# LED_Controller.net
KiCad netlist of a schematic drawn in EAGLE
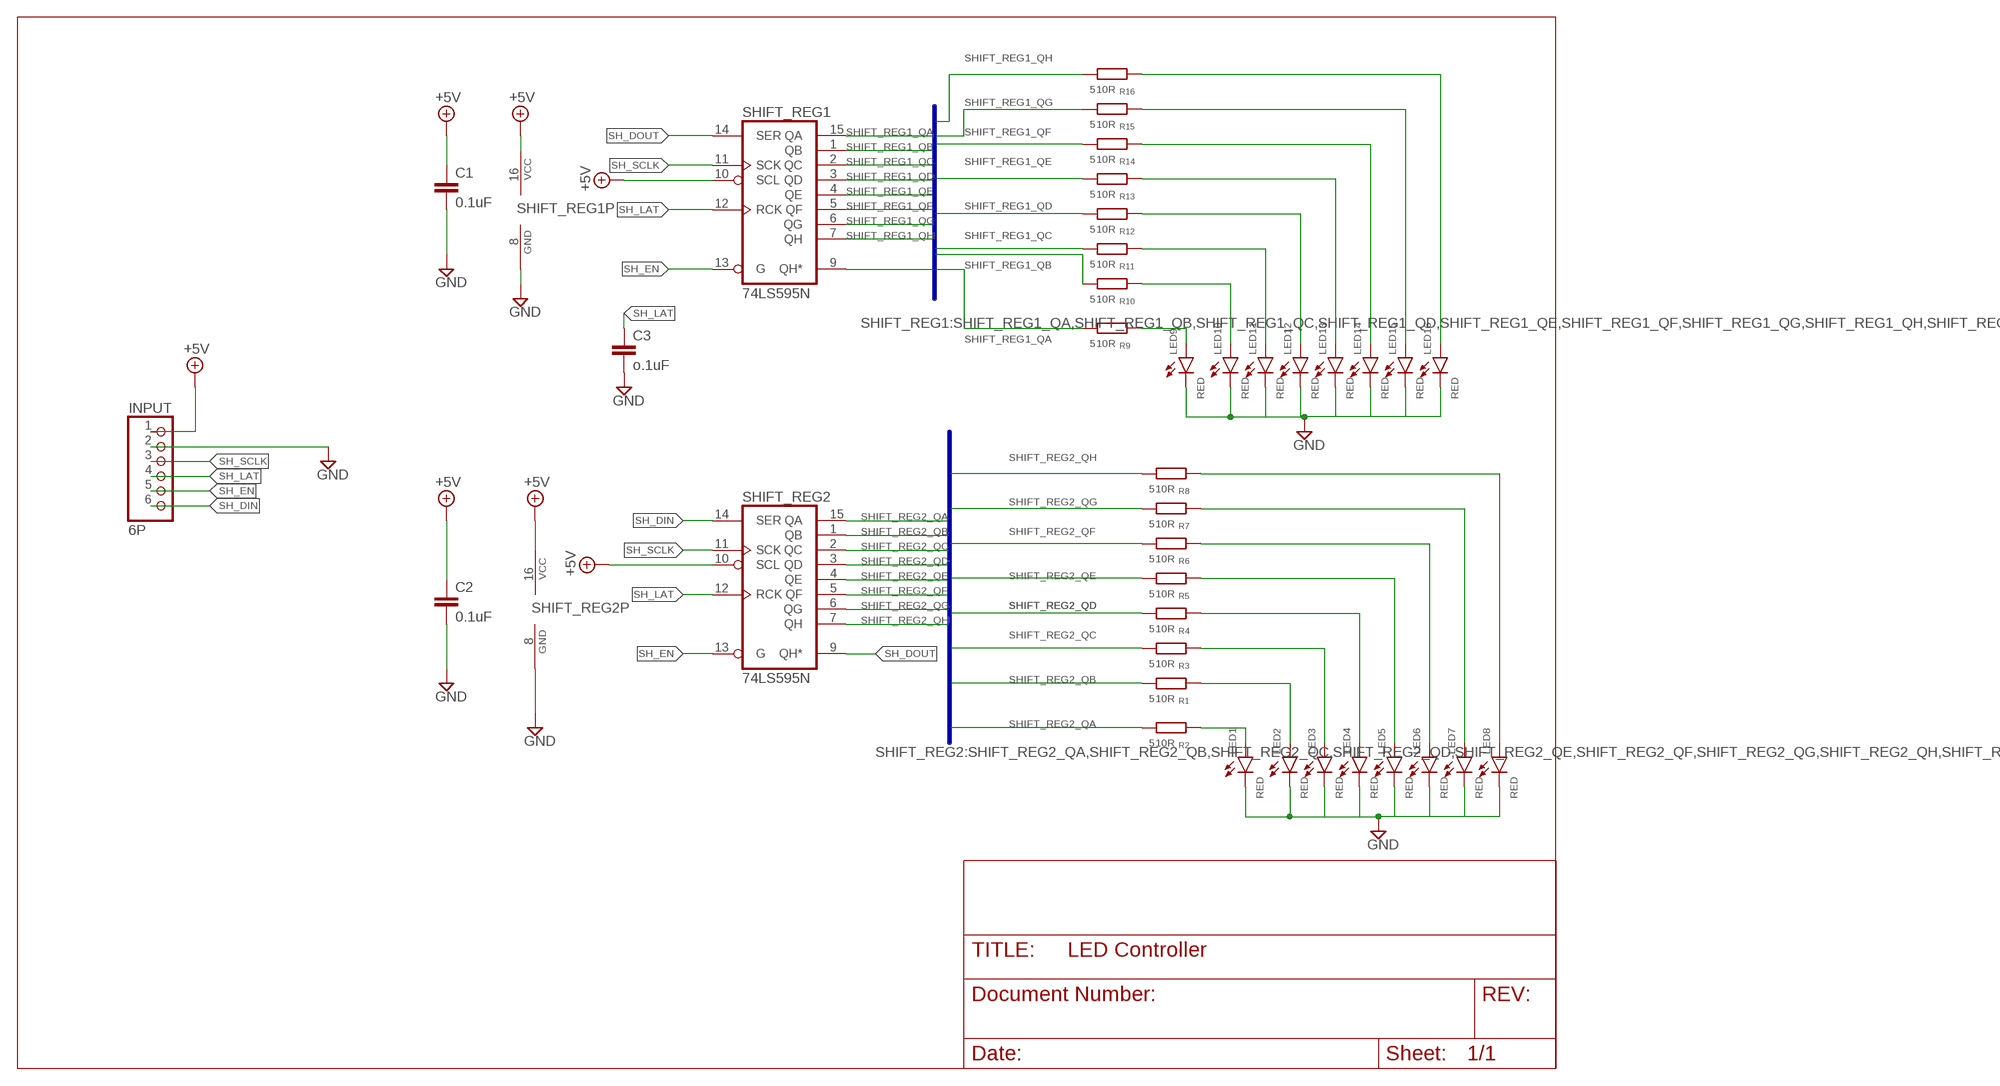
[diagram p0: schematic, sheet 1]

(export (version "E")
  (design (tool "Eeschema 10.0.6"))
  (components
    (comp (ref "C1")
      (value "0.1uF")
      (footprint "eagle-import:C050-030X075")
      (libsource (lib "eagle-import") (part "C-EU050-030X075"))
    )
    (comp (ref "C2")
      (value "0.1uF")
      (footprint "eagle-import:C050-030X075")
      (libsource (lib "eagle-import") (part "C-EU050-030X075"))
    )
    (comp (ref "C3")
      (value "o.1uF")
      (footprint "eagle-import:C050-030X075")
      (libsource (lib "eagle-import") (part "C-EU050-030X075"))
    )
    (comp (ref "INPUT")
      (value "6P")
      (footprint "eagle-import:1X06_90")
      (libsource (lib "eagle-import") (part "PINHD-1X6/90"))
    )
    (comp (ref "LED1")
      (value "RED")
      (footprint "eagle-import:LED5MM")
      (libsource (lib "eagle-import") (part "LED5MM"))
    )
    (comp (ref "LED2")
      (value "RED")
      (footprint "eagle-import:LED5MM")
      (libsource (lib "eagle-import") (part "LED5MM"))
    )
    (comp (ref "LED3")
      (value "RED")
      (footprint "eagle-import:LED5MM")
      (libsource (lib "eagle-import") (part "LED5MM"))
    )
    (comp (ref "LED4")
      (value "RED")
      (footprint "eagle-import:LED5MM")
      (libsource (lib "eagle-import") (part "LED5MM"))
    )
    (comp (ref "LED5")
      (value "RED")
      (footprint "eagle-import:LED5MM")
      (libsource (lib "eagle-import") (part "LED5MM"))
    )
    (comp (ref "LED6")
      (value "RED")
      (footprint "eagle-import:LED5MM")
      (libsource (lib "eagle-import") (part "LED5MM"))
    )
    (comp (ref "LED7")
      (value "RED")
      (footprint "eagle-import:LED5MM")
      (libsource (lib "eagle-import") (part "LED5MM"))
    )
    (comp (ref "LED8")
      (value "RED")
      (footprint "eagle-import:LED5MM")
      (libsource (lib "eagle-import") (part "LED5MM"))
    )
    (comp (ref "LED9")
      (value "RED")
      (footprint "eagle-import:LED5MM")
      (libsource (lib "eagle-import") (part "LED5MM"))
    )
    (comp (ref "LED10")
      (value "RED")
      (footprint "eagle-import:LED5MM")
      (libsource (lib "eagle-import") (part "LED5MM"))
    )
    (comp (ref "LED11")
      (value "RED")
      (footprint "eagle-import:LED5MM")
      (libsource (lib "eagle-import") (part "LED5MM"))
    )
    (comp (ref "LED12")
      (value "RED")
      (footprint "eagle-import:LED5MM")
      (libsource (lib "eagle-import") (part "LED5MM"))
    )
    (comp (ref "LED13")
      (value "RED")
      (footprint "eagle-import:LED5MM")
      (libsource (lib "eagle-import") (part "LED5MM"))
    )
    (comp (ref "LED14")
      (value "RED")
      (footprint "eagle-import:LED5MM")
      (libsource (lib "eagle-import") (part "LED5MM"))
    )
    (comp (ref "LED15")
      (value "RED")
      (footprint "eagle-import:LED5MM")
      (libsource (lib "eagle-import") (part "LED5MM"))
    )
    (comp (ref "LED16")
      (value "RED")
      (footprint "eagle-import:LED5MM")
      (libsource (lib "eagle-import") (part "LED5MM"))
    )
    (comp (ref "R1")
      (value "510R")
      (footprint "eagle-import:0207_10")
      (libsource (lib "eagle-import") (part "R-EU_0207/10"))
    )
    (comp (ref "R2")
      (value "510R")
      (footprint "eagle-import:0207_10")
      (libsource (lib "eagle-import") (part "R-EU_0207/10"))
    )
    (comp (ref "R3")
      (value "510R")
      (footprint "eagle-import:0207_10")
      (libsource (lib "eagle-import") (part "R-EU_0207/10"))
    )
    (comp (ref "R4")
      (value "510R")
      (footprint "eagle-import:0207_10")
      (libsource (lib "eagle-import") (part "R-EU_0207/10"))
    )
    (comp (ref "R5")
      (value "510R")
      (footprint "eagle-import:0207_10")
      (libsource (lib "eagle-import") (part "R-EU_0207/10"))
    )
    (comp (ref "R6")
      (value "510R")
      (footprint "eagle-import:0207_10")
      (libsource (lib "eagle-import") (part "R-EU_0207/10"))
    )
    (comp (ref "R7")
      (value "510R")
      (footprint "eagle-import:0207_10")
      (libsource (lib "eagle-import") (part "R-EU_0207/10"))
    )
    (comp (ref "R8")
      (value "510R")
      (footprint "eagle-import:0207_10")
      (libsource (lib "eagle-import") (part "R-EU_0207/10"))
    )
    (comp (ref "R9")
      (value "510R")
      (footprint "eagle-import:0207_10")
      (libsource (lib "eagle-import") (part "R-EU_0207/10"))
    )
    (comp (ref "R10")
      (value "510R")
      (footprint "eagle-import:0207_10")
      (libsource (lib "eagle-import") (part "R-EU_0207/10"))
    )
    (comp (ref "R11")
      (value "510R")
      (footprint "eagle-import:0207_10")
      (libsource (lib "eagle-import") (part "R-EU_0207/10"))
    )
    (comp (ref "R12")
      (value "510R")
      (footprint "eagle-import:0207_10")
      (libsource (lib "eagle-import") (part "R-EU_0207/10"))
    )
    (comp (ref "R13")
      (value "510R")
      (footprint "eagle-import:0207_10")
      (libsource (lib "eagle-import") (part "R-EU_0207/10"))
    )
    (comp (ref "R14")
      (value "510R")
      (footprint "eagle-import:0207_10")
      (libsource (lib "eagle-import") (part "R-EU_0207/10"))
    )
    (comp (ref "R15")
      (value "510R")
      (footprint "eagle-import:0207_10")
      (libsource (lib "eagle-import") (part "R-EU_0207/10"))
    )
    (comp (ref "R16")
      (value "510R")
      (footprint "eagle-import:0207_10")
      (libsource (lib "eagle-import") (part "R-EU_0207/10"))
    )
    (comp (ref "SHIFT_REG1")
      (value "74LS595N")
      (footprint "eagle-import:DIL16")
      (libsource (lib "eagle-import") (part "74595NLS"))
    )
    (comp (ref "SHIFT_REG2")
      (value "74LS595N")
      (footprint "eagle-import:DIL16")
      (libsource (lib "eagle-import") (part "74595NLS"))
    )
  )
  (nets
    (net (code "5") (name "+5V") (class "Default")
      (node (ref "C1") (pin "1") (pinfunction "1_1") (pintype "passive"))
      (node (ref "C2") (pin "1") (pinfunction "1_1") (pintype "passive"))
      (node (ref "INPUT") (pin "1") (pinfunction "1_1") (pintype "passive"))
      (node (ref "SHIFT_REG1") (pin "10") (pinfunction "SCL_10") (pintype "input"))
      (node (ref "SHIFT_REG1") (pin "16") (pinfunction "VCC_16") (pintype "power_in"))
      (node (ref "SHIFT_REG2") (pin "10") (pinfunction "SCL_10") (pintype "input"))
      (node (ref "SHIFT_REG2") (pin "16") (pinfunction "VCC_16") (pintype "power_in"))
    )
    (net (code "6") (name "/SHIFT_REG1_QA") (class "Default")
      (node (ref "R9") (pin "1") (pinfunction "1_1") (pintype "passive"))
      (node (ref "SHIFT_REG1") (pin "15") (pinfunction "QA_15") (pintype "tri_state"))
    )
    (net (code "7") (name "/SHIFT_REG1_QB") (class "Default")
      (node (ref "R10") (pin "1") (pinfunction "1_1") (pintype "passive"))
      (node (ref "SHIFT_REG1") (pin "1") (pinfunction "QB_1") (pintype "tri_state"))
    )
    (net (code "8") (name "/SHIFT_REG1_QC") (class "Default")
      (node (ref "R11") (pin "1") (pinfunction "1_1") (pintype "passive"))
      (node (ref "SHIFT_REG1") (pin "2") (pinfunction "QC_2") (pintype "tri_state"))
    )
    (net (code "9") (name "/SHIFT_REG1_QD") (class "Default")
      (node (ref "R12") (pin "1") (pinfunction "1_1") (pintype "passive"))
      (node (ref "SHIFT_REG1") (pin "3") (pinfunction "QD_3") (pintype "tri_state"))
    )
    (net (code "10") (name "/SHIFT_REG1_QE") (class "Default")
      (node (ref "R13") (pin "1") (pinfunction "1_1") (pintype "passive"))
      (node (ref "SHIFT_REG1") (pin "4") (pinfunction "QE_4") (pintype "tri_state"))
    )
    (net (code "11") (name "/SHIFT_REG1_QF") (class "Default")
      (node (ref "R14") (pin "1") (pinfunction "1_1") (pintype "passive"))
      (node (ref "SHIFT_REG1") (pin "5") (pinfunction "QF_5") (pintype "tri_state"))
    )
    (net (code "12") (name "/SHIFT_REG1_QG") (class "Default")
      (node (ref "R15") (pin "1") (pinfunction "1_1") (pintype "passive"))
      (node (ref "SHIFT_REG1") (pin "6") (pinfunction "QG_6") (pintype "tri_state"))
    )
    (net (code "13") (name "/SHIFT_REG1_QH") (class "Default")
      (node (ref "R16") (pin "1") (pinfunction "1_1") (pintype "passive"))
      (node (ref "SHIFT_REG1") (pin "7") (pinfunction "QH_7") (pintype "tri_state"))
    )
    (net (code "14") (name "/SHIFT_REG2_QA") (class "Default")
      (node (ref "R2") (pin "1") (pinfunction "1_1") (pintype "passive"))
      (node (ref "SHIFT_REG2") (pin "15") (pinfunction "QA_15") (pintype "tri_state"))
    )
    (net (code "15") (name "/SHIFT_REG2_QB") (class "Default")
      (node (ref "R1") (pin "1") (pinfunction "1_1") (pintype "passive"))
      (node (ref "SHIFT_REG2") (pin "1") (pinfunction "QB_1") (pintype "tri_state"))
    )
    (net (code "16") (name "/SHIFT_REG2_QC") (class "Default")
      (node (ref "R3") (pin "1") (pinfunction "1_1") (pintype "passive"))
      (node (ref "SHIFT_REG2") (pin "2") (pinfunction "QC_2") (pintype "tri_state"))
    )
    (net (code "17") (name "/SHIFT_REG2_QD") (class "Default")
      (node (ref "R4") (pin "1") (pinfunction "1_1") (pintype "passive"))
      (node (ref "SHIFT_REG2") (pin "3") (pinfunction "QD_3") (pintype "tri_state"))
    )
    (net (code "18") (name "/SHIFT_REG2_QE") (class "Default")
      (node (ref "R5") (pin "1") (pinfunction "1_1") (pintype "passive"))
      (node (ref "SHIFT_REG2") (pin "4") (pinfunction "QE_4") (pintype "tri_state"))
    )
    (net (code "19") (name "/SHIFT_REG2_QF") (class "Default")
      (node (ref "R6") (pin "1") (pinfunction "1_1") (pintype "passive"))
      (node (ref "SHIFT_REG2") (pin "5") (pinfunction "QF_5") (pintype "tri_state"))
    )
    (net (code "20") (name "/SHIFT_REG2_QG") (class "Default")
      (node (ref "R7") (pin "1") (pinfunction "1_1") (pintype "passive"))
      (node (ref "SHIFT_REG2") (pin "6") (pinfunction "QG_6") (pintype "tri_state"))
    )
    (net (code "21") (name "/SHIFT_REG2_QH") (class "Default")
      (node (ref "R8") (pin "1") (pinfunction "1_1") (pintype "passive"))
      (node (ref "SHIFT_REG2") (pin "7") (pinfunction "QH_7") (pintype "tri_state"))
    )
    (net (code "24") (name "GND") (class "Default")
      (node (ref "C1") (pin "2") (pinfunction "2_2") (pintype "passive"))
      (node (ref "C2") (pin "2") (pinfunction "2_2") (pintype "passive"))
      (node (ref "C3") (pin "2") (pinfunction "2_2") (pintype "passive"))
      (node (ref "INPUT") (pin "2") (pinfunction "2_2") (pintype "passive"))
      (node (ref "LED1") (pin "K") (pinfunction "C_K") (pintype "passive"))
      (node (ref "LED10") (pin "K") (pinfunction "C_K") (pintype "passive"))
      (node (ref "LED11") (pin "K") (pinfunction "C_K") (pintype "passive"))
      (node (ref "LED12") (pin "K") (pinfunction "C_K") (pintype "passive"))
      (node (ref "LED13") (pin "K") (pinfunction "C_K") (pintype "passive"))
      (node (ref "LED14") (pin "K") (pinfunction "C_K") (pintype "passive"))
      (node (ref "LED15") (pin "K") (pinfunction "C_K") (pintype "passive"))
      (node (ref "LED16") (pin "K") (pinfunction "C_K") (pintype "passive"))
      (node (ref "LED2") (pin "K") (pinfunction "C_K") (pintype "passive"))
      (node (ref "LED3") (pin "K") (pinfunction "C_K") (pintype "passive"))
      (node (ref "LED4") (pin "K") (pinfunction "C_K") (pintype "passive"))
      (node (ref "LED5") (pin "K") (pinfunction "C_K") (pintype "passive"))
      (node (ref "LED6") (pin "K") (pinfunction "C_K") (pintype "passive"))
      (node (ref "LED7") (pin "K") (pinfunction "C_K") (pintype "passive"))
      (node (ref "LED8") (pin "K") (pinfunction "C_K") (pintype "passive"))
      (node (ref "LED9") (pin "K") (pinfunction "C_K") (pintype "passive"))
      (node (ref "SHIFT_REG1") (pin "8") (pinfunction "GND_8") (pintype "power_in"))
      (node (ref "SHIFT_REG2") (pin "8") (pinfunction "GND_8") (pintype "power_in"))
    )
    (net (code "25") (name "Net-(LED1-PadA)") (class "Default")
      (node (ref "LED1") (pin "A") (pinfunction "A_A") (pintype "passive"))
      (node (ref "R2") (pin "2") (pinfunction "2_2") (pintype "passive"))
    )
    (net (code "26") (name "Net-(LED2-PadA)") (class "Default")
      (node (ref "LED2") (pin "A") (pinfunction "A_A") (pintype "passive"))
      (node (ref "R1") (pin "2") (pinfunction "2_2") (pintype "passive"))
    )
    (net (code "27") (name "Net-(LED3-PadA)") (class "Default")
      (node (ref "LED3") (pin "A") (pinfunction "A_A") (pintype "passive"))
      (node (ref "R3") (pin "2") (pinfunction "2_2") (pintype "passive"))
    )
    (net (code "28") (name "Net-(LED4-PadA)") (class "Default")
      (node (ref "LED4") (pin "A") (pinfunction "A_A") (pintype "passive"))
      (node (ref "R4") (pin "2") (pinfunction "2_2") (pintype "passive"))
    )
    (net (code "29") (name "Net-(LED5-PadA)") (class "Default")
      (node (ref "LED5") (pin "A") (pinfunction "A_A") (pintype "passive"))
      (node (ref "R5") (pin "2") (pinfunction "2_2") (pintype "passive"))
    )
    (net (code "30") (name "Net-(LED6-PadA)") (class "Default")
      (node (ref "LED6") (pin "A") (pinfunction "A_A") (pintype "passive"))
      (node (ref "R6") (pin "2") (pinfunction "2_2") (pintype "passive"))
    )
    (net (code "31") (name "Net-(LED7-PadA)") (class "Default")
      (node (ref "LED7") (pin "A") (pinfunction "A_A") (pintype "passive"))
      (node (ref "R7") (pin "2") (pinfunction "2_2") (pintype "passive"))
    )
    (net (code "32") (name "Net-(LED8-PadA)") (class "Default")
      (node (ref "LED8") (pin "A") (pinfunction "A_A") (pintype "passive"))
      (node (ref "R8") (pin "2") (pinfunction "2_2") (pintype "passive"))
    )
    (net (code "33") (name "Net-(LED9-PadA)") (class "Default")
      (node (ref "LED9") (pin "A") (pinfunction "A_A") (pintype "passive"))
      (node (ref "R9") (pin "2") (pinfunction "2_2") (pintype "passive"))
    )
    (net (code "34") (name "Net-(LED10-PadA)") (class "Default")
      (node (ref "LED10") (pin "A") (pinfunction "A_A") (pintype "passive"))
      (node (ref "R10") (pin "2") (pinfunction "2_2") (pintype "passive"))
    )
    (net (code "35") (name "Net-(LED11-PadA)") (class "Default")
      (node (ref "LED11") (pin "A") (pinfunction "A_A") (pintype "passive"))
      (node (ref "R11") (pin "2") (pinfunction "2_2") (pintype "passive"))
    )
    (net (code "36") (name "Net-(LED12-PadA)") (class "Default")
      (node (ref "LED12") (pin "A") (pinfunction "A_A") (pintype "passive"))
      (node (ref "R12") (pin "2") (pinfunction "2_2") (pintype "passive"))
    )
    (net (code "37") (name "Net-(LED13-PadA)") (class "Default")
      (node (ref "LED13") (pin "A") (pinfunction "A_A") (pintype "passive"))
      (node (ref "R13") (pin "2") (pinfunction "2_2") (pintype "passive"))
    )
    (net (code "38") (name "Net-(LED14-PadA)") (class "Default")
      (node (ref "LED14") (pin "A") (pinfunction "A_A") (pintype "passive"))
      (node (ref "R14") (pin "2") (pinfunction "2_2") (pintype "passive"))
    )
    (net (code "39") (name "Net-(LED15-PadA)") (class "Default")
      (node (ref "LED15") (pin "A") (pinfunction "A_A") (pintype "passive"))
      (node (ref "R15") (pin "2") (pinfunction "2_2") (pintype "passive"))
    )
    (net (code "40") (name "Net-(LED16-PadA)") (class "Default")
      (node (ref "LED16") (pin "A") (pinfunction "A_A") (pintype "passive"))
      (node (ref "R16") (pin "2") (pinfunction "2_2") (pintype "passive"))
    )
    (net (code "41") (name "SH_DIN") (class "Default")
      (node (ref "INPUT") (pin "6") (pinfunction "6_6") (pintype "passive"))
      (node (ref "SHIFT_REG2") (pin "14") (pinfunction "SER_14") (pintype "input"))
    )
    (net (code "42") (name "SH_DOUT") (class "Default")
      (node (ref "SHIFT_REG1") (pin "14") (pinfunction "SER_14") (pintype "input"))
      (node (ref "SHIFT_REG2") (pin "9") (pinfunction "QH*_9") (pintype "tri_state"))
    )
    (net (code "43") (name "SH_EN") (class "Default")
      (node (ref "INPUT") (pin "5") (pinfunction "5_5") (pintype "passive"))
      (node (ref "SHIFT_REG1") (pin "13") (pinfunction "G_13") (pintype "input"))
      (node (ref "SHIFT_REG2") (pin "13") (pinfunction "G_13") (pintype "input"))
    )
    (net (code "44") (name "SH_LAT") (class "Default")
      (node (ref "C3") (pin "1") (pinfunction "1_1") (pintype "passive"))
      (node (ref "INPUT") (pin "4") (pinfunction "4_4") (pintype "passive"))
      (node (ref "SHIFT_REG1") (pin "12") (pinfunction "RCK_12") (pintype "input"))
      (node (ref "SHIFT_REG2") (pin "12") (pinfunction "RCK_12") (pintype "input"))
    )
    (net (code "45") (name "SH_SCLK") (class "Default")
      (node (ref "INPUT") (pin "3") (pinfunction "3_3") (pintype "passive"))
      (node (ref "SHIFT_REG1") (pin "11") (pinfunction "SCK_11") (pintype "input"))
      (node (ref "SHIFT_REG2") (pin "11") (pinfunction "SCK_11") (pintype "input"))
    )
    (net (code "46") (name "unconnected-(SHIFT_REG1A-QH*-Pad9)") (class "Default")
      (node (ref "SHIFT_REG1") (pin "9") (pinfunction "QH*_9") (pintype "tri_state"))
    )
  )
)
